# LCD_PCB.net
KiCad netlist of a schematic drawn in Altium Designer
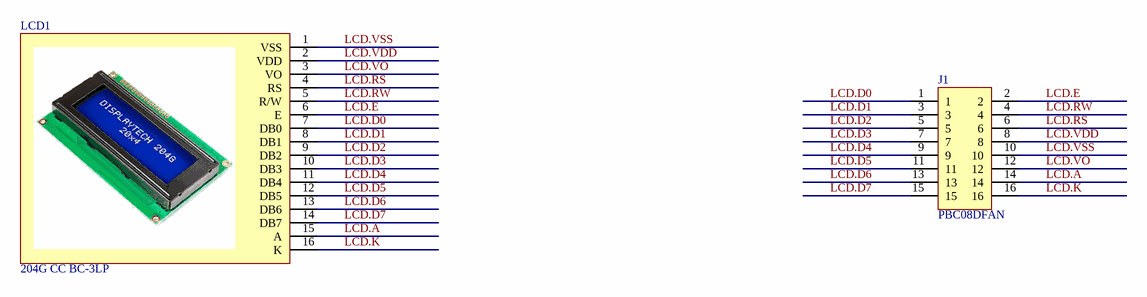
[diagram p0: LCD PCB.SchDoc]

(export (version "E")
  (design (tool "Eeschema 10.0.6"))
  (components
    (comp (ref "J1")
      (value "PBC08DFAN")
      (footprint "SULLINS_PBC08DFAN")
      (description "Connector Header Through Hole 16 position 0.100\" (2.54mm)")
      (fields (field (name "VENDOR 1 PART NUMBER") "S2211E-08-ND") (field (name "CREATEDBY") "Judd Foster"))
      (libsource (lib "Component Library") (part "Term,Header,2x8 Pin,2.54mm,Top,Thru"))
    )
    (comp (ref "LCD1")
      (value "204G CC BC-3LP")
      (footprint "DISPLAYTECH_204G CC BC-3LP")
      (fields
        (field (name "VENDOR 1 PART NUMBER") "1756-204GCCBC-3LP-ND")
        (field (name "CREATEDBY") "Judd Foster")
      )
      (libsource (lib "Component Library") (part "DISP,Char,LCD,20x4,204G CC BC-3LP"))
    )
  )
  (nets
    (net (code "1") (name "/LCD.A") (class "Default")
      (node (ref "J1") (pin "14") (pinfunction "14_14") (pintype "passive"))
      (node (ref "LCD1") (pin "15") (pinfunction "A_15") (pintype "power_in"))
    )
    (net (code "2") (name "/LCD.D0") (class "Default")
      (node (ref "J1") (pin "1") (pinfunction "1_1") (pintype "passive"))
      (node (ref "LCD1") (pin "7") (pinfunction "DB0_7") (pintype "power_in"))
    )
    (net (code "3") (name "/LCD.D1") (class "Default")
      (node (ref "J1") (pin "3") (pinfunction "3_3") (pintype "passive"))
      (node (ref "LCD1") (pin "8") (pinfunction "DB1_8") (pintype "power_in"))
    )
    (net (code "4") (name "/LCD.D2") (class "Default")
      (node (ref "J1") (pin "5") (pinfunction "5_5") (pintype "passive"))
      (node (ref "LCD1") (pin "9") (pinfunction "DB2_9") (pintype "power_in"))
    )
    (net (code "5") (name "/LCD.D3") (class "Default")
      (node (ref "J1") (pin "7") (pinfunction "7_7") (pintype "passive"))
      (node (ref "LCD1") (pin "10") (pinfunction "DB3_10") (pintype "power_in"))
    )
    (net (code "6") (name "/LCD.D4") (class "Default")
      (node (ref "J1") (pin "9") (pinfunction "9_9") (pintype "passive"))
      (node (ref "LCD1") (pin "11") (pinfunction "DB4_11") (pintype "power_in"))
    )
    (net (code "7") (name "/LCD.D5") (class "Default")
      (node (ref "J1") (pin "11") (pinfunction "11_11") (pintype "passive"))
      (node (ref "LCD1") (pin "12") (pinfunction "DB5_12") (pintype "power_in"))
    )
    (net (code "8") (name "/LCD.D6") (class "Default")
      (node (ref "J1") (pin "13") (pinfunction "13_13") (pintype "passive"))
      (node (ref "LCD1") (pin "13") (pinfunction "DB6_13") (pintype "power_in"))
    )
    (net (code "9") (name "/LCD.D7") (class "Default")
      (node (ref "J1") (pin "15") (pinfunction "15_15") (pintype "passive"))
      (node (ref "LCD1") (pin "14") (pinfunction "DB7_14") (pintype "power_in"))
    )
    (net (code "10") (name "/LCD.E") (class "Default")
      (node (ref "J1") (pin "2") (pinfunction "2_2") (pintype "passive"))
      (node (ref "LCD1") (pin "6") (pinfunction "E_6") (pintype "power_in"))
    )
    (net (code "11") (name "/LCD.K") (class "Default")
      (node (ref "J1") (pin "16") (pinfunction "16_16") (pintype "passive"))
      (node (ref "LCD1") (pin "16") (pinfunction "K_16") (pintype "power_in"))
    )
    (net (code "12") (name "/LCD.RS") (class "Default")
      (node (ref "J1") (pin "6") (pinfunction "6_6") (pintype "passive"))
      (node (ref "LCD1") (pin "4") (pinfunction "RS_4") (pintype "power_in"))
    )
    (net (code "13") (name "/LCD.RW") (class "Default")
      (node (ref "J1") (pin "4") (pinfunction "4_4") (pintype "passive"))
      (node (ref "LCD1") (pin "5") (pinfunction "R/W_5") (pintype "power_in"))
    )
    (net (code "14") (name "/LCD.VDD") (class "Default")
      (node (ref "J1") (pin "8") (pinfunction "8_8") (pintype "passive"))
      (node (ref "LCD1") (pin "2") (pinfunction "VDD_2") (pintype "power_in"))
    )
    (net (code "15") (name "/LCD.VO") (class "Default")
      (node (ref "J1") (pin "12") (pinfunction "12_12") (pintype "passive"))
      (node (ref "LCD1") (pin "3") (pinfunction "VO_3") (pintype "power_in"))
    )
    (net (code "16") (name "/LCD.VSS") (class "Default")
      (node (ref "J1") (pin "10") (pinfunction "10_10") (pintype "passive"))
      (node (ref "LCD1") (pin "1") (pinfunction "VSS_1") (pintype "power_in"))
    )
  )
)
